# GRHV_Double_25v_KC.net
KiCad netlist of a schematic drawn in Altium Designer
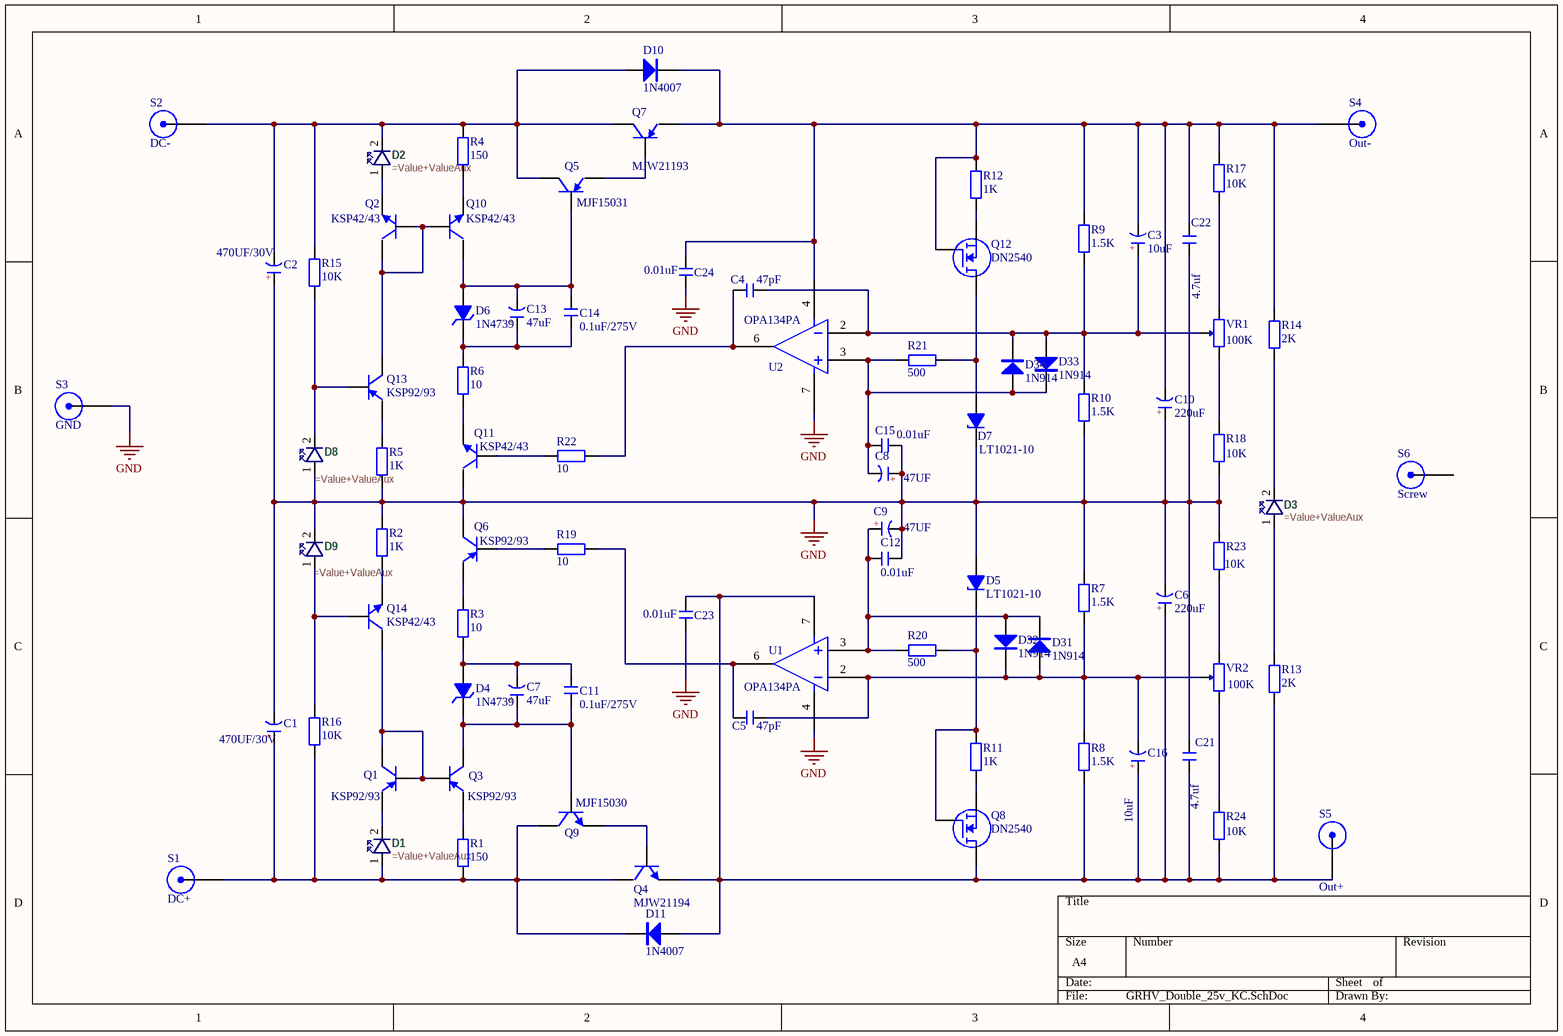
[diagram p0: GRHV_Double_25v_KC.SchDoc]

(export (version "E")
  (design (tool "Eeschema 10.0.6"))
  (components
    (comp (ref "C1")
      (value "470UF/30V")
      (footprint "CAP 11*35*60")
      (description "直插电解电容")
      (fields (field (name "版权归属") "源创客"))
      (libsource (lib "电阻-电容-电感") (part "C-CAP"))
    )
    (comp (ref "C2")
      (value "470UF/30V")
      (footprint "CAP 11*35*60")
      (description "直插电解电容")
      (fields (field (name "版权归属") "源创客"))
      (libsource (lib "电阻-电容-电感") (part "C-CAP"))
    )
    (comp (ref "C3")
      (value "10uF")
      (footprint "CAP 7.0*16.5*20")
      (description "直插电解电容")
      (fields (field (name "版权归属") "源创客"))
      (libsource (lib "电阻-电容-电感") (part "C-CAP"))
    )
    (comp (ref "C4")
      (value "47pF")
      (footprint "CBB 6.3*6.3*5")
      (description "CBB电容")
      (fields (field (name "版权归属") "源创客"))
      (libsource (lib "电阻-电容-电感") (part "C-CBB"))
    )
    (comp (ref "C5")
      (value "47pF")
      (footprint "CBB 6.3*6.3*5")
      (description "CBB电容")
      (fields (field (name "版权归属") "源创客"))
      (libsource (lib "电阻-电容-电感") (part "C-CBB"))
    )
    (comp (ref "C6")
      (value "220uF")
      (footprint "CAP 7.0*16.5*20")
      (description "直插电解电容")
      (fields (field (name "版权归属") "源创客"))
      (libsource (lib "电阻-电容-电感") (part "C-CAP"))
    )
    (comp (ref "C7")
      (value "47uF")
      (footprint "CAP 2.5*6.3*11.2")
      (description "直插电解电容")
      (fields (field (name "版权归属") "源创客"))
      (libsource (lib "电阻-电容-电感") (part "C-CAP"))
    )
    (comp (ref "C8")
      (value "47UF")
      (footprint "CAP 2.5*6.3*11.2")
      (description "直插电解电容")
      (fields (field (name "版权归属") "源创客"))
      (libsource (lib "") (part "C-CAP_1"))
    )
    (comp (ref "C9")
      (value "47UF")
      (footprint "CAP 2.5*6.3*11.2")
      (description "直插电解电容")
      (fields (field (name "版权归属") "源创客"))
      (libsource (lib "") (part "C-CAP_1"))
    )
    (comp (ref "C10")
      (value "220uF")
      (footprint "CAP 7.0*16.5*20")
      (description "直插电解电容")
      (fields (field (name "版权归属") "源创客"))
      (libsource (lib "电阻-电容-电感") (part "C-CAP"))
    )
    (comp (ref "C11")
      (value "0.1uF/275V")
      (footprint "CBB 6.3*6.3*5")
      (description "CBB电容")
      (fields (field (name "版权归属") "源创客"))
      (libsource (lib "电阻-电容-电感") (part "C-CBB"))
    )
    (comp (ref "C12")
      (value "0.01uF")
      (footprint "CBB 6.3*6.3*5")
      (description "CBB电容")
      (fields (field (name "版权归属") "源创客"))
      (libsource (lib "电阻-电容-电感") (part "C-CBB"))
    )
    (comp (ref "C13")
      (value "47uF")
      (footprint "CAP 2.5*6.3*11.2")
      (description "直插电解电容")
      (fields (field (name "版权归属") "源创客"))
      (libsource (lib "电阻-电容-电感") (part "C-CAP"))
    )
    (comp (ref "C14")
      (value "0.1uF/275V")
      (footprint "CBB 6.3*6.3*5")
      (description "CBB电容")
      (fields (field (name "版权归属") "源创客"))
      (libsource (lib "电阻-电容-电感") (part "C-CBB"))
    )
    (comp (ref "C15")
      (value "0.01uF")
      (footprint "CBB 6.3*6.3*5")
      (description "CBB电容")
      (fields (field (name "版权归属") "源创客"))
      (libsource (lib "电阻-电容-电感") (part "C-CBB"))
    )
    (comp (ref "C16")
      (value "10uF")
      (footprint "CAP 7.0*16.5*20")
      (description "直插电解电容")
      (fields (field (name "版权归属") "源创客"))
      (libsource (lib "电阻-电容-电感") (part "C-CAP"))
    )
    (comp (ref "C21")
      (value "4.7uf")
      (footprint "CBB 7.2*7.2*13")
      (description "MKS薄膜电容")
      (libsource (lib "电阻-电容-电感") (part "C-MKS"))
    )
    (comp (ref "C22")
      (value "4.7uf")
      (footprint "CBB 7.2*7.2*13")
      (description "MKS薄膜电容")
      (libsource (lib "电阻-电容-电感") (part "C-MKS"))
    )
    (comp (ref "C23")
      (value "0.01uF")
      (footprint "CBB 6.3*6.3*5")
      (description "CBB电容")
      (fields (field (name "版权归属") "源创客"))
      (libsource (lib "电阻-电容-电感") (part "C-CBB"))
    )
    (comp (ref "C24")
      (value "0.01uF")
      (footprint "CBB 6.3*6.3*5")
      (description "CBB电容")
      (fields (field (name "版权归属") "源创客"))
      (libsource (lib "电阻-电容-电感") (part "C-CBB"))
    )
    (comp (ref "D1")
      (value "~")
      (footprint "LED 3MM-R")
      (description "直插式LED")
      (libsource (lib "LED") (part "LED"))
    )
    (comp (ref "D2")
      (value "~")
      (footprint "LED 3MM-R")
      (description "直插式LED")
      (libsource (lib "LED") (part "LED"))
    )
    (comp (ref "D3")
      (value "~")
      (footprint "LED 3MM-R")
      (description "直插式LED")
      (libsource (lib "LED") (part "LED"))
    )
    (comp (ref "D4")
      (value "1N4739")
      (footprint "DO-41")
      (description "9.1V/1W稳压管")
      (libsource (lib "二极管-整流桥") (part "1N4739"))
    )
    (comp (ref "D5")
      (value "LT1021-10")
      (footprint "DIP8-300_MH")
      (description "10V Precision Reference 2 Pin Config")
      (libsource (lib "电压参考") (part "LT1021-10-2P"))
    )
    (comp (ref "D6")
      (value "1N4739")
      (footprint "DO-41")
      (description "9.1V/1W稳压管")
      (libsource (lib "二极管-整流桥") (part "1N4739"))
    )
    (comp (ref "D7")
      (value "LT1021-10")
      (footprint "DIP8-300_MH")
      (description "10V Precision Reference 2 Pin Config")
      (libsource (lib "电压参考") (part "LT1021-10-2P"))
    )
    (comp (ref "D8")
      (value "~")
      (footprint "LED 3MM-R")
      (description "直插式LED")
      (libsource (lib "LED") (part "LED"))
    )
    (comp (ref "D9")
      (value "~")
      (footprint "LED 3MM-R")
      (description "直插式LED")
      (libsource (lib "LED") (part "LED"))
    )
    (comp (ref "D10")
      (value "1N4007")
      (footprint "DO-41")
      (description "整流二极管")
      (fields (field (name "版权归属") "源创客"))
      (libsource (lib "二极管-整流桥") (part "1N4007"))
    )
    (comp (ref "D11")
      (value "1N4007")
      (footprint "DO-41")
      (description "整流二极管")
      (fields (field (name "版权归属") "源创客"))
      (libsource (lib "二极管-整流桥") (part "1N4007"))
    )
    (comp (ref "D31")
      (value "1N914")
      (footprint "DO-35")
      (description "高速开关管 1V/0.25W")
      (libsource (lib "二极管-整流桥") (part "1N914"))
    )
    (comp (ref "D32")
      (value "1N914")
      (footprint "DO-35")
      (description "高速开关管 1V/0.25W")
      (libsource (lib "二极管-整流桥") (part "1N914"))
    )
    (comp (ref "D33")
      (value "1N914")
      (footprint "DO-35")
      (description "高速开关管 1V/0.25W")
      (libsource (lib "二极管-整流桥") (part "1N914"))
    )
    (comp (ref "D34")
      (value "1N914")
      (footprint "DO-35")
      (description "高速开关管 1V/0.25W")
      (libsource (lib "二极管-整流桥") (part "1N914"))
    )
    (comp (ref "Q1")
      (value "KSP92/93")
      (footprint "TO92A")
      (description "High Voltage PNP Transistor")
      (libsource (lib "三极管") (part "KSP92/93"))
    )
    (comp (ref "Q2")
      (value "KSP42/43")
      (footprint "TO92A")
      (description "High Voltage NPN Transistor")
      (libsource (lib "三极管") (part "KSP42/43"))
    )
    (comp (ref "Q3")
      (value "KSP92/93")
      (footprint "TO92A")
      (description "High Voltage PNP Transistor")
      (libsource (lib "三极管") (part "KSP92/93"))
    )
    (comp (ref "Q4")
      (value "MJW21194")
      (footprint "TO247V-HeatSink")
      (description "Power NPN Transistor")
      (libsource (lib "三极管") (part "MJW21194"))
    )
    (comp (ref "Q5")
      (value "MJF15031")
      (footprint "TO220V")
      (description "Power PNP Transistor")
      (libsource (lib "三极管") (part "MJF15031"))
    )
    (comp (ref "Q6")
      (value "KSP92/93")
      (footprint "TO92A")
      (description "High Voltage PNP Transistor")
      (libsource (lib "三极管") (part "KSP92/93"))
    )
    (comp (ref "Q7")
      (value "MJW21193")
      (footprint "TO247V-HeatSink")
      (description "Power PNP Transistor")
      (libsource (lib "三极管") (part "MJW21193"))
    )
    (comp (ref "Q8")
      (value "DN2540")
      (footprint "TO92A")
      (description "N沟道耗尽型DMOS场效应管 400V/150ma")
      (libsource (lib "场效应管") (part "DN2540"))
    )
    (comp (ref "Q9")
      (value "MJF15030")
      (footprint "TO220V")
      (description "Power NPN Transistor")
      (libsource (lib "三极管") (part "MJF15030"))
    )
    (comp (ref "Q10")
      (value "KSP42/43")
      (footprint "TO92A")
      (description "High Voltage NPN Transistor")
      (libsource (lib "三极管") (part "KSP42/43"))
    )
    (comp (ref "Q11")
      (value "KSP42/43")
      (footprint "TO92A")
      (description "High Voltage NPN Transistor")
      (libsource (lib "三极管") (part "KSP42/43"))
    )
    (comp (ref "Q12")
      (value "DN2540")
      (footprint "TO92A")
      (description "N沟道耗尽型DMOS场效应管 400V/150ma")
      (libsource (lib "场效应管") (part "DN2540"))
    )
    (comp (ref "Q13")
      (value "KSP92/93")
      (footprint "TO92A")
      (description "High Voltage PNP Transistor")
      (libsource (lib "三极管") (part "KSP92/93"))
    )
    (comp (ref "Q14")
      (value "KSP42/43")
      (footprint "TO92A")
      (description "High Voltage NPN Transistor")
      (libsource (lib "三极管") (part "KSP42/43"))
    )
    (comp (ref "R1")
      (value "150")
      (footprint "RS 1/4W")
      (description "直插色环电阻")
      (fields (field (name "版权归属") "源创客"))
      (libsource (lib "电阻-电容-电感") (part "R-CRR"))
    )
    (comp (ref "R2")
      (value "1K")
      (footprint "RS 1/4W")
      (description "直插色环电阻")
      (fields (field (name "版权归属") "源创客"))
      (libsource (lib "电阻-电容-电感") (part "R-CRR"))
    )
    (comp (ref "R3")
      (value "10")
      (footprint "RS 1/4W")
      (description "直插色环电阻")
      (fields (field (name "版权归属") "源创客"))
      (libsource (lib "电阻-电容-电感") (part "R-CRR"))
    )
    (comp (ref "R4")
      (value "150")
      (footprint "RS 1/4W")
      (description "直插色环电阻")
      (fields (field (name "版权归属") "源创客"))
      (libsource (lib "电阻-电容-电感") (part "R-CRR"))
    )
    (comp (ref "R5")
      (value "1K")
      (footprint "RS 1/4W")
      (description "直插色环电阻")
      (fields (field (name "版权归属") "源创客"))
      (libsource (lib "电阻-电容-电感") (part "R-CRR"))
    )
    (comp (ref "R6")
      (value "10")
      (footprint "RS 1/4W")
      (description "直插色环电阻")
      (fields (field (name "版权归属") "源创客"))
      (libsource (lib "电阻-电容-电感") (part "R-CRR"))
    )
    (comp (ref "R7")
      (value "1.5K")
      (footprint "RS 1/4W")
      (description "直插色环电阻")
      (fields (field (name "版权归属") "源创客"))
      (libsource (lib "电阻-电容-电感") (part "R-CRR"))
    )
    (comp (ref "R8")
      (value "1.5K")
      (footprint "RS 1/4W")
      (description "直插色环电阻")
      (fields (field (name "版权归属") "源创客"))
      (libsource (lib "电阻-电容-电感") (part "R-CRR"))
    )
    (comp (ref "R9")
      (value "1.5K")
      (footprint "RS 1/4W")
      (description "直插色环电阻")
      (fields (field (name "版权归属") "源创客"))
      (libsource (lib "电阻-电容-电感") (part "R-CRR"))
    )
    (comp (ref "R10")
      (value "1.5K")
      (footprint "RS 1/4W")
      (description "直插色环电阻")
      (fields (field (name "版权归属") "源创客"))
      (libsource (lib "电阻-电容-电感") (part "R-CRR"))
    )
    (comp (ref "R11")
      (value "1K")
      (footprint "RS 1/4W-V3")
      (description "直插色环电阻")
      (fields (field (name "版权归属") "源创客"))
      (libsource (lib "电阻-电容-电感") (part "R-CRR"))
    )
    (comp (ref "R12")
      (value "1K")
      (footprint "RS 1/4W-V3")
      (description "直插色环电阻")
      (fields (field (name "版权归属") "源创客"))
      (libsource (lib "电阻-电容-电感") (part "R-CRR"))
    )
    (comp (ref "R13")
      (value "2K")
      (footprint "RS 1/4W")
      (description "直插色环电阻")
      (fields (field (name "版权归属") "源创客"))
      (libsource (lib "电阻-电容-电感") (part "R-CRR"))
    )
    (comp (ref "R14")
      (value "2K")
      (footprint "RS 1/4W")
      (description "直插色环电阻")
      (fields (field (name "版权归属") "源创客"))
      (libsource (lib "电阻-电容-电感") (part "R-CRR"))
    )
    (comp (ref "R15")
      (value "10K")
      (footprint "RS 1/4W")
      (description "直插色环电阻")
      (fields (field (name "版权归属") "源创客"))
      (libsource (lib "电阻-电容-电感") (part "R-CRR"))
    )
    (comp (ref "R16")
      (value "10K")
      (footprint "RS 1/4W")
      (description "直插色环电阻")
      (fields (field (name "版权归属") "源创客"))
      (libsource (lib "电阻-电容-电感") (part "R-CRR"))
    )
    (comp (ref "R17")
      (value "10K")
      (footprint "RS 1/4W-V3")
      (description "直插色环电阻")
      (fields (field (name "版权归属") "源创客"))
      (libsource (lib "电阻-电容-电感") (part "R-CRR"))
    )
    (comp (ref "R18")
      (value "10K")
      (footprint "RS 1/4W")
      (description "直插色环电阻")
      (fields (field (name "版权归属") "源创客"))
      (libsource (lib "电阻-电容-电感") (part "R-CRR"))
    )
    (comp (ref "R19")
      (value "10")
      (footprint "RS 1/4W")
      (description "直插色环电阻")
      (fields (field (name "版权归属") "源创客"))
      (libsource (lib "电阻-电容-电感") (part "R-CRR"))
    )
    (comp (ref "R20")
      (value "500")
      (footprint "RS 1/4W-V3")
      (description "直插色环电阻")
      (fields (field (name "版权归属") "源创客"))
      (libsource (lib "电阻-电容-电感") (part "R-CRR"))
    )
    (comp (ref "R21")
      (value "500")
      (footprint "RS 1/4W-V3")
      (description "直插色环电阻")
      (fields (field (name "版权归属") "源创客"))
      (libsource (lib "电阻-电容-电感") (part "R-CRR"))
    )
    (comp (ref "R22")
      (value "10")
      (footprint "RS 1/4W")
      (description "直插色环电阻")
      (fields (field (name "版权归属") "源创客"))
      (libsource (lib "电阻-电容-电感") (part "R-CRR"))
    )
    (comp (ref "R23")
      (value "10K")
      (footprint "RS 1/4W")
      (description "直插色环电阻")
      (fields (field (name "版权归属") "源创客"))
      (libsource (lib "电阻-电容-电感") (part "R-CRR"))
    )
    (comp (ref "R24")
      (value "10K")
      (footprint "RS 1/4W-V3")
      (description "直插色环电阻")
      (fields (field (name "版权归属") "源创客"))
      (libsource (lib "电阻-电容-电感") (part "R-CRR"))
    )
    (comp (ref "S1")
      (value "DC+")
      (footprint "Screw-M3")
      (description "Screw Connector")
      (libsource (lib "Connectors") (part "ScrewConnector"))
    )
    (comp (ref "S2")
      (value "DC-")
      (footprint "Screw-M3")
      (description "Screw Connector")
      (libsource (lib "Connectors") (part "ScrewConnector"))
    )
    (comp (ref "S3")
      (value "GND")
      (footprint "Screw-M3")
      (description "Screw Connector")
      (libsource (lib "Connectors") (part "ScrewConnector"))
    )
    (comp (ref "S4")
      (value "Out-")
      (footprint "Screw-M3")
      (description "Screw Connector")
      (libsource (lib "Connectors") (part "ScrewConnector"))
    )
    (comp (ref "S5")
      (value "Out+")
      (footprint "Screw-M3")
      (description "Screw Connector")
      (libsource (lib "Connectors") (part "ScrewConnector"))
    )
    (comp (ref "S6")
      (value "Screw")
      (footprint "Screw-M3")
      (description "Screw Connector")
      (libsource (lib "Connectors") (part "ScrewConnector"))
    )
    (comp (ref "U1") (value "OPA134PA") (footprint "DIP8-300_MH") (libsource (lib "运放") (part "OPA134PA")))
    (comp (ref "U2") (value "OPA134PA") (footprint "DIP8-300_MH") (libsource (lib "运放") (part "OPA134PA")))
    (comp (ref "VR1")
      (value "100K")
      (footprint "RS 1/2W-VR")
      (description "直插可调电阻-顶调")
      (fields (field (name "Comment") "VR-W"))
      (libsource (lib "电阻-电容-电感") (part "VR-W"))
    )
    (comp (ref "VR2")
      (value "100K")
      (footprint "RS 1/2W-VR")
      (description "直插可调电阻-顶调")
      (fields (field (name "Comment") "VR-W"))
      (libsource (lib "电阻-电容-电感") (part "VR-W"))
    )
  )
  (nets
    (net (code "1") (name "GND") (class "Default")
      (node (ref "C1") (pin "2") (pinfunction "K_2") (pintype "passive"))
      (node (ref "C10") (pin "1") (pinfunction "A_1") (pintype "passive"))
      (node (ref "C12") (pin "2") (pinfunction "2_2") (pintype "passive"))
      (node (ref "C15") (pin "2") (pinfunction "2_2") (pintype "passive"))
      (node (ref "C2") (pin "1") (pinfunction "A_1") (pintype "passive"))
      (node (ref "C21") (pin "2") (pinfunction "2_2") (pintype "passive"))
      (node (ref "C22") (pin "1") (pinfunction "1_1") (pintype "passive"))
      (node (ref "C23") (pin "1") (pinfunction "1_1") (pintype "passive"))
      (node (ref "C24") (pin "1") (pinfunction "1_1") (pintype "passive"))
      (node (ref "C6") (pin "2") (pinfunction "K_2") (pintype "passive"))
      (node (ref "C8") (pin "1") (pinfunction "A_1") (pintype "passive"))
      (node (ref "C9") (pin "2") (pinfunction "K_2") (pintype "passive"))
      (node (ref "D5") (pin "4") (pinfunction "A_4") (pintype "passive"))
      (node (ref "D7") (pin "6") (pinfunction "K_6") (pintype "passive"))
      (node (ref "D8") (pin "1") (pinfunction "A_1") (pintype "passive"))
      (node (ref "D9") (pin "2") (pinfunction "K_2") (pintype "passive"))
      (node (ref "Q11") (pin "3") (pinfunction "C_3") (pintype "passive"))
      (node (ref "Q6") (pin "3") (pinfunction "C_3") (pintype "passive"))
      (node (ref "R10") (pin "1") (pinfunction "1_1") (pintype "passive"))
      (node (ref "R18") (pin "1") (pinfunction "1_1") (pintype "passive"))
      (node (ref "R2") (pin "2") (pinfunction "2_2") (pintype "passive"))
      (node (ref "R23") (pin "2") (pinfunction "2_2") (pintype "passive"))
      (node (ref "R5") (pin "1") (pinfunction "1_1") (pintype "passive"))
      (node (ref "R7") (pin "2") (pinfunction "2_2") (pintype "passive"))
      (node (ref "S3") (pin "1") (pinfunction "X_1") (pintype "passive"))
      (node (ref "U1") (pin "4") (pinfunction "V-_4") (pintype "passive"))
      (node (ref "U2") (pin "7") (pinfunction "V+_7") (pintype "passive"))
    )
    (net (code "2") (name "Net-(C1-A)") (class "Default")
      (node (ref "C1") (pin "1") (pinfunction "A_1") (pintype "passive"))
      (node (ref "D1") (pin "1") (pinfunction "A_1") (pintype "passive"))
      (node (ref "D11") (pin "2") (pinfunction "K_2") (pintype "passive"))
      (node (ref "Q4") (pin "2") (pinfunction "C_2") (pintype "passive"))
      (node (ref "Q9") (pin "2") (pinfunction "C_2") (pintype "passive"))
      (node (ref "R1") (pin "1") (pinfunction "1_1") (pintype "passive"))
      (node (ref "R16") (pin "1") (pinfunction "1_1") (pintype "passive"))
      (node (ref "S1") (pin "1") (pinfunction "X_1") (pintype "passive"))
    )
    (net (code "3") (name "Net-(C2-K)") (class "Default")
      (node (ref "C2") (pin "2") (pinfunction "K_2") (pintype "passive"))
      (node (ref "D10") (pin "1") (pinfunction "A_1") (pintype "passive"))
      (node (ref "D2") (pin "2") (pinfunction "K_2") (pintype "passive"))
      (node (ref "Q5") (pin "2") (pinfunction "C_2") (pintype "passive"))
      (node (ref "Q7") (pin "2") (pinfunction "C_2") (pintype "passive"))
      (node (ref "R15") (pin "2") (pinfunction "2_2") (pintype "passive"))
      (node (ref "R4") (pin "2") (pinfunction "2_2") (pintype "passive"))
      (node (ref "S2") (pin "1") (pinfunction "X_1") (pintype "passive"))
    )
    (net (code "4") (name "Net-(C3-A)") (class "Default")
      (node (ref "C3") (pin "1") (pinfunction "A_1") (pintype "passive"))
      (node (ref "C4") (pin "2") (pinfunction "2_2") (pintype "passive"))
      (node (ref "D33") (pin "1") (pinfunction "A_1") (pintype "passive"))
      (node (ref "D34") (pin "2") (pinfunction "K_2") (pintype "passive"))
      (node (ref "R10") (pin "2") (pinfunction "2_2") (pintype "passive"))
      (node (ref "R9") (pin "1") (pinfunction "1_1") (pintype "passive"))
      (node (ref "U2") (pin "2") (pinfunction "-in_2") (pintype "passive"))
      (node (ref "VR1") (pin "3") (pinfunction "3_3") (pintype "passive"))
    )
    (net (code "5") (name "Net-(C7-A)") (class "Default")
      (node (ref "C11") (pin "1") (pinfunction "1_1") (pintype "passive"))
      (node (ref "C7") (pin "1") (pinfunction "A_1") (pintype "passive"))
      (node (ref "D4") (pin "2") (pinfunction "K_2") (pintype "passive"))
      (node (ref "Q3") (pin "3") (pinfunction "C_3") (pintype "passive"))
      (node (ref "Q9") (pin "1") (pinfunction "B_1") (pintype "passive"))
    )
    (net (code "6") (name "Net-(C7-K)") (class "Default")
      (node (ref "C11") (pin "2") (pinfunction "2_2") (pintype "passive"))
      (node (ref "C7") (pin "2") (pinfunction "K_2") (pintype "passive"))
      (node (ref "D4") (pin "1") (pinfunction "A_1") (pintype "passive"))
      (node (ref "R3") (pin "1") (pinfunction "1_1") (pintype "passive"))
    )
    (net (code "7") (name "Net-(C8-K)") (class "Default")
      (node (ref "C15") (pin "1") (pinfunction "1_1") (pintype "passive"))
      (node (ref "C8") (pin "2") (pinfunction "K_2") (pintype "passive"))
      (node (ref "D33") (pin "2") (pinfunction "K_2") (pintype "passive"))
      (node (ref "D34") (pin "1") (pinfunction "A_1") (pintype "passive"))
      (node (ref "R21") (pin "1") (pinfunction "1_1") (pintype "passive"))
      (node (ref "U2") (pin "3") (pinfunction "+in_3") (pintype "passive"))
    )
    (net (code "8") (name "Net-(C9-A)") (class "Default")
      (node (ref "C12") (pin "1") (pinfunction "1_1") (pintype "passive"))
      (node (ref "C9") (pin "1") (pinfunction "A_1") (pintype "passive"))
      (node (ref "D31") (pin "2") (pinfunction "K_2") (pintype "passive"))
      (node (ref "D32") (pin "1") (pinfunction "A_1") (pintype "passive"))
      (node (ref "R20") (pin "1") (pinfunction "1_1") (pintype "passive"))
      (node (ref "U1") (pin "3") (pinfunction "+in_3") (pintype "passive"))
    )
    (net (code "9") (name "Net-(C10-K)") (class "Default")
      (node (ref "C10") (pin "2") (pinfunction "K_2") (pintype "passive"))
      (node (ref "C22") (pin "2") (pinfunction "2_2") (pintype "passive"))
      (node (ref "C24") (pin "2") (pinfunction "2_2") (pintype "passive"))
      (node (ref "C3") (pin "2") (pinfunction "K_2") (pintype "passive"))
      (node (ref "D10") (pin "2") (pinfunction "K_2") (pintype "passive"))
      (node (ref "Q12") (pin "2") (pinfunction "G_2") (pintype "passive"))
      (node (ref "Q7") (pin "3") (pinfunction "E_3") (pintype "passive"))
      (node (ref "R12") (pin "2") (pinfunction "2_2") (pintype "passive"))
      (node (ref "R14") (pin "2") (pinfunction "2_2") (pintype "passive"))
      (node (ref "R17") (pin "2") (pinfunction "2_2") (pintype "passive"))
      (node (ref "R9") (pin "2") (pinfunction "2_2") (pintype "passive"))
      (node (ref "S4") (pin "1") (pinfunction "X_1") (pintype "passive"))
      (node (ref "U2") (pin "4") (pinfunction "V-_4") (pintype "passive"))
    )
    (net (code "10") (name "Net-(C13-A)") (class "Default")
      (node (ref "C13") (pin "1") (pinfunction "A_1") (pintype "passive"))
      (node (ref "C14") (pin "1") (pinfunction "1_1") (pintype "passive"))
      (node (ref "D6") (pin "2") (pinfunction "K_2") (pintype "passive"))
      (node (ref "R6") (pin "2") (pinfunction "2_2") (pintype "passive"))
    )
    (net (code "11") (name "Net-(C13-K)") (class "Default")
      (node (ref "C13") (pin "2") (pinfunction "K_2") (pintype "passive"))
      (node (ref "C14") (pin "2") (pinfunction "2_2") (pintype "passive"))
      (node (ref "D6") (pin "1") (pinfunction "A_1") (pintype "passive"))
      (node (ref "Q10") (pin "3") (pinfunction "C_3") (pintype "passive"))
      (node (ref "Q5") (pin "1") (pinfunction "B_1") (pintype "passive"))
    )
    (net (code "12") (name "Net-(C16-A)") (class "Default")
      (node (ref "C16") (pin "1") (pinfunction "A_1") (pintype "passive"))
      (node (ref "C21") (pin "1") (pinfunction "1_1") (pintype "passive"))
      (node (ref "C23") (pin "2") (pinfunction "2_2") (pintype "passive"))
      (node (ref "C6") (pin "1") (pinfunction "A_1") (pintype "passive"))
      (node (ref "D11") (pin "1") (pinfunction "A_1") (pintype "passive"))
      (node (ref "Q4") (pin "3") (pinfunction "E_3") (pintype "passive"))
      (node (ref "Q8") (pin "3") (pinfunction "D_3") (pintype "passive"))
      (node (ref "R13") (pin "2") (pinfunction "2_2") (pintype "passive"))
      (node (ref "R24") (pin "1") (pinfunction "1_1") (pintype "passive"))
      (node (ref "R8") (pin "1") (pinfunction "1_1") (pintype "passive"))
      (node (ref "S5") (pin "1") (pinfunction "X_1") (pintype "passive"))
      (node (ref "U1") (pin "7") (pinfunction "V+_7") (pintype "passive"))
    )
    (net (code "13") (name "Net-(C16-K)") (class "Default")
      (node (ref "C16") (pin "2") (pinfunction "K_2") (pintype "passive"))
      (node (ref "C5") (pin "2") (pinfunction "2_2") (pintype "passive"))
      (node (ref "D31") (pin "1") (pinfunction "A_1") (pintype "passive"))
      (node (ref "D32") (pin "2") (pinfunction "K_2") (pintype "passive"))
      (node (ref "R7") (pin "1") (pinfunction "1_1") (pintype "passive"))
      (node (ref "R8") (pin "2") (pinfunction "2_2") (pintype "passive"))
      (node (ref "U1") (pin "2") (pinfunction "-in_2") (pintype "passive"))
      (node (ref "VR2") (pin "3") (pinfunction "3_3") (pintype "passive"))
    )
    (net (code "14") (name "Net-(D1-K)") (class "Default")
      (node (ref "D1") (pin "2") (pinfunction "K_2") (pintype "passive"))
      (node (ref "Q1") (pin "1") (pinfunction "E_1") (pintype "passive"))
    )
    (net (code "15") (name "Net-(D2-A)") (class "Default")
      (node (ref "D2") (pin "1") (pinfunction "A_1") (pintype "passive"))
      (node (ref "Q2") (pin "1") (pinfunction "E_1") (pintype "passive"))
    )
    (net (code "16") (name "Net-(D3-A)") (class "Default")
      (node (ref "D3") (pin "1") (pinfunction "A_1") (pintype "passive"))
      (node (ref "R13") (pin "1") (pinfunction "1_1") (pintype "passive"))
    )
    (net (code "17") (name "Net-(D3-K)") (class "Default")
      (node (ref "D3") (pin "2") (pinfunction "K_2") (pintype "passive"))
      (node (ref "R14") (pin "1") (pinfunction "1_1") (pintype "passive"))
    )
    (net (code "18") (name "Net-(D5-K)") (class "Default")
      (node (ref "D5") (pin "6") (pinfunction "K_6") (pintype "passive"))
      (node (ref "Q8") (pin "2") (pinfunction "G_2") (pintype "passive"))
      (node (ref "R11") (pin "2") (pinfunction "2_2") (pintype "passive"))
      (node (ref "R20") (pin "2") (pinfunction "2_2") (pintype "passive"))
    )
    (net (code "19") (name "Net-(D7-A)") (class "Default")
      (node (ref "D7") (pin "4") (pinfunction "A_4") (pintype "passive"))
      (node (ref "Q12") (pin "3") (pinfunction "D_3") (pintype "passive"))
      (node (ref "R21") (pin "2") (pinfunction "2_2") (pintype "passive"))
    )
    (net (code "20") (name "Net-(D8-K)") (class "Default")
      (node (ref "D8") (pin "2") (pinfunction "K_2") (pintype "passive"))
      (node (ref "Q13") (pin "2") (pinfunction "B_2") (pintype "passive"))
      (node (ref "R15") (pin "1") (pinfunction "1_1") (pintype "passive"))
    )
    (net (code "21") (name "Net-(D9-A)") (class "Default")
      (node (ref "D9") (pin "1") (pinfunction "A_1") (pintype "passive"))
      (node (ref "Q14") (pin "2") (pinfunction "B_2") (pintype "passive"))
      (node (ref "R16") (pin "2") (pinfunction "2_2") (pintype "passive"))
    )
    (net (code "22") (name "Net-(Q1-B)") (class "Default")
      (node (ref "Q1") (pin "2") (pinfunction "B_2") (pintype "passive"))
      (node (ref "Q1") (pin "3") (pinfunction "C_3") (pintype "passive"))
      (node (ref "Q14") (pin "3") (pinfunction "C_3") (pintype "passive"))
      (node (ref "Q3") (pin "2") (pinfunction "B_2") (pintype "passive"))
    )
    (net (code "23") (name "Net-(Q3-E)") (class "Default")
      (node (ref "Q3") (pin "1") (pinfunction "E_1") (pintype "passive"))
      (node (ref "R1") (pin "2") (pinfunction "2_2") (pintype "passive"))
    )
    (net (code "24") (name "Net-(Q4-B)") (class "Default")
      (node (ref "Q4") (pin "1") (pinfunction "B_1") (pintype "passive"))
      (node (ref "Q9") (pin "3") (pinfunction "E_3") (pintype "passive"))
    )
    (net (code "25") (name "Net-(Q5-E)") (class "Default")
      (node (ref "Q5") (pin "3") (pinfunction "E_3") (pintype "passive"))
      (node (ref "Q7") (pin "1") (pinfunction "B_1") (pintype "passive"))
    )
    (net (code "26") (name "Net-(Q6-B)") (class "Default")
      (node (ref "Q6") (pin "2") (pinfunction "B_2") (pintype "passive"))
      (node (ref "R19") (pin "1") (pinfunction "1_1") (pintype "passive"))
    )
    (net (code "27") (name "Net-(Q6-E)") (class "Default")
      (node (ref "Q6") (pin "1") (pinfunction "E_1") (pintype "passive"))
      (node (ref "R3") (pin "2") (pinfunction "2_2") (pintype "passive"))
    )
    (net (code "28") (name "Net-(Q8-S)") (class "Default")
      (node (ref "Q8") (pin "1") (pinfunction "S_1") (pintype "passive"))
      (node (ref "R11") (pin "1") (pinfunction "1_1") (pintype "passive"))
    )
    (net (code "29") (name "Net-(Q10-B)") (class "Default")
      (node (ref "Q10") (pin "2") (pinfunction "B_2") (pintype "passive"))
      (node (ref "Q13") (pin "3") (pinfunction "C_3") (pintype "passive"))
      (node (ref "Q2") (pin "2") (pinfunction "B_2") (pintype "passive"))
      (node (ref "Q2") (pin "3") (pinfunction "C_3") (pintype "passive"))
    )
    (net (code "30") (name "Net-(Q10-E)") (class "Default")
      (node (ref "Q10") (pin "1") (pinfunction "E_1") (pintype "passive"))
      (node (ref "R4") (pin "1") (pinfunction "1_1") (pintype "passive"))
    )
    (net (code "31") (name "Net-(Q11-B)") (class "Default")
      (node (ref "Q11") (pin "2") (pinfunction "B_2") (pintype "passive"))
      (node (ref "R22") (pin "1") (pinfunction "1_1") (pintype "passive"))
    )
    (net (code "32") (name "Net-(Q11-E)") (class "Default")
      (node (ref "Q11") (pin "1") (pinfunction "E_1") (pintype "passive"))
      (node (ref "R6") (pin "1") (pinfunction "1_1") (pintype "passive"))
    )
    (net (code "33") (name "Net-(Q12-S)") (class "Default")
      (node (ref "Q12") (pin "1") (pinfunction "S_1") (pintype "passive"))
      (node (ref "R12") (pin "1") (pinfunction "1_1") (pintype "passive"))
    )
    (net (code "34") (name "Net-(Q13-E)") (class "Default")
      (node (ref "Q13") (pin "1") (pinfunction "E_1") (pintype "passive"))
      (node (ref "R5") (pin "2") (pinfunction "2_2") (pintype "passive"))
    )
    (net (code "35") (name "Net-(Q14-E)") (class "Default")
      (node (ref "Q14") (pin "1") (pinfunction "E_1") (pintype "passive"))
      (node (ref "R2") (pin "1") (pinfunction "1_1") (pintype "passive"))
    )
    (net (code "36") (name "Net-(R17-Pad1)") (class "Default")
      (node (ref "R17") (pin "1") (pinfunction "1_1") (pintype "passive"))
      (node (ref "VR1") (pin "2") (pinfunction "2_2") (pintype "passive"))
    )
    (net (code "37") (name "Net-(R18-Pad2)") (class "Default")
      (node (ref "R18") (pin "2") (pinfunction "2_2") (pintype "passive"))
      (node (ref "VR1") (pin "1") (pinfunction "1_1") (pintype "passive"))
    )
    (net (code "38") (name "Net-(R23-Pad1)") (class "Default")
      (node (ref "R23") (pin "1") (pinfunction "1_1") (pintype "passive"))
      (node (ref "VR2") (pin "2") (pinfunction "2_2") (pintype "passive"))
    )
    (net (code "39") (name "Net-(R24-Pad2)") (class "Default")
      (node (ref "R24") (pin "2") (pinfunction "2_2") (pintype "passive"))
      (node (ref "VR2") (pin "1") (pinfunction "1_1") (pintype "passive"))
    )
    (net (code "40") (name "Net-(U1-out)") (class "Default")
      (node (ref "C5") (pin "1") (pinfunction "1_1") (pintype "passive"))
      (node (ref "R19") (pin "2") (pinfunction "2_2") (pintype "passive"))
      (node (ref "U1") (pin "6") (pinfunction "out_6") (pintype "passive"))
    )
    (net (code "41") (name "Net-(U2-out)") (class "Default")
      (node (ref "C4") (pin "1") (pinfunction "1_1") (pintype "passive"))
      (node (ref "R22") (pin "2") (pinfunction "2_2") (pintype "passive"))
      (node (ref "U2") (pin "6") (pinfunction "out_6") (pintype "passive"))
    )
    (net (code "42") (name "unconnected-(S6-X-Pad1)") (class "Default")
      (node (ref "S6") (pin "1") (pinfunction "X_1") (pintype "passive"))
    )
  )
)
